# sch.net
KiCad netlist of a schematic drawn in EasyEDA
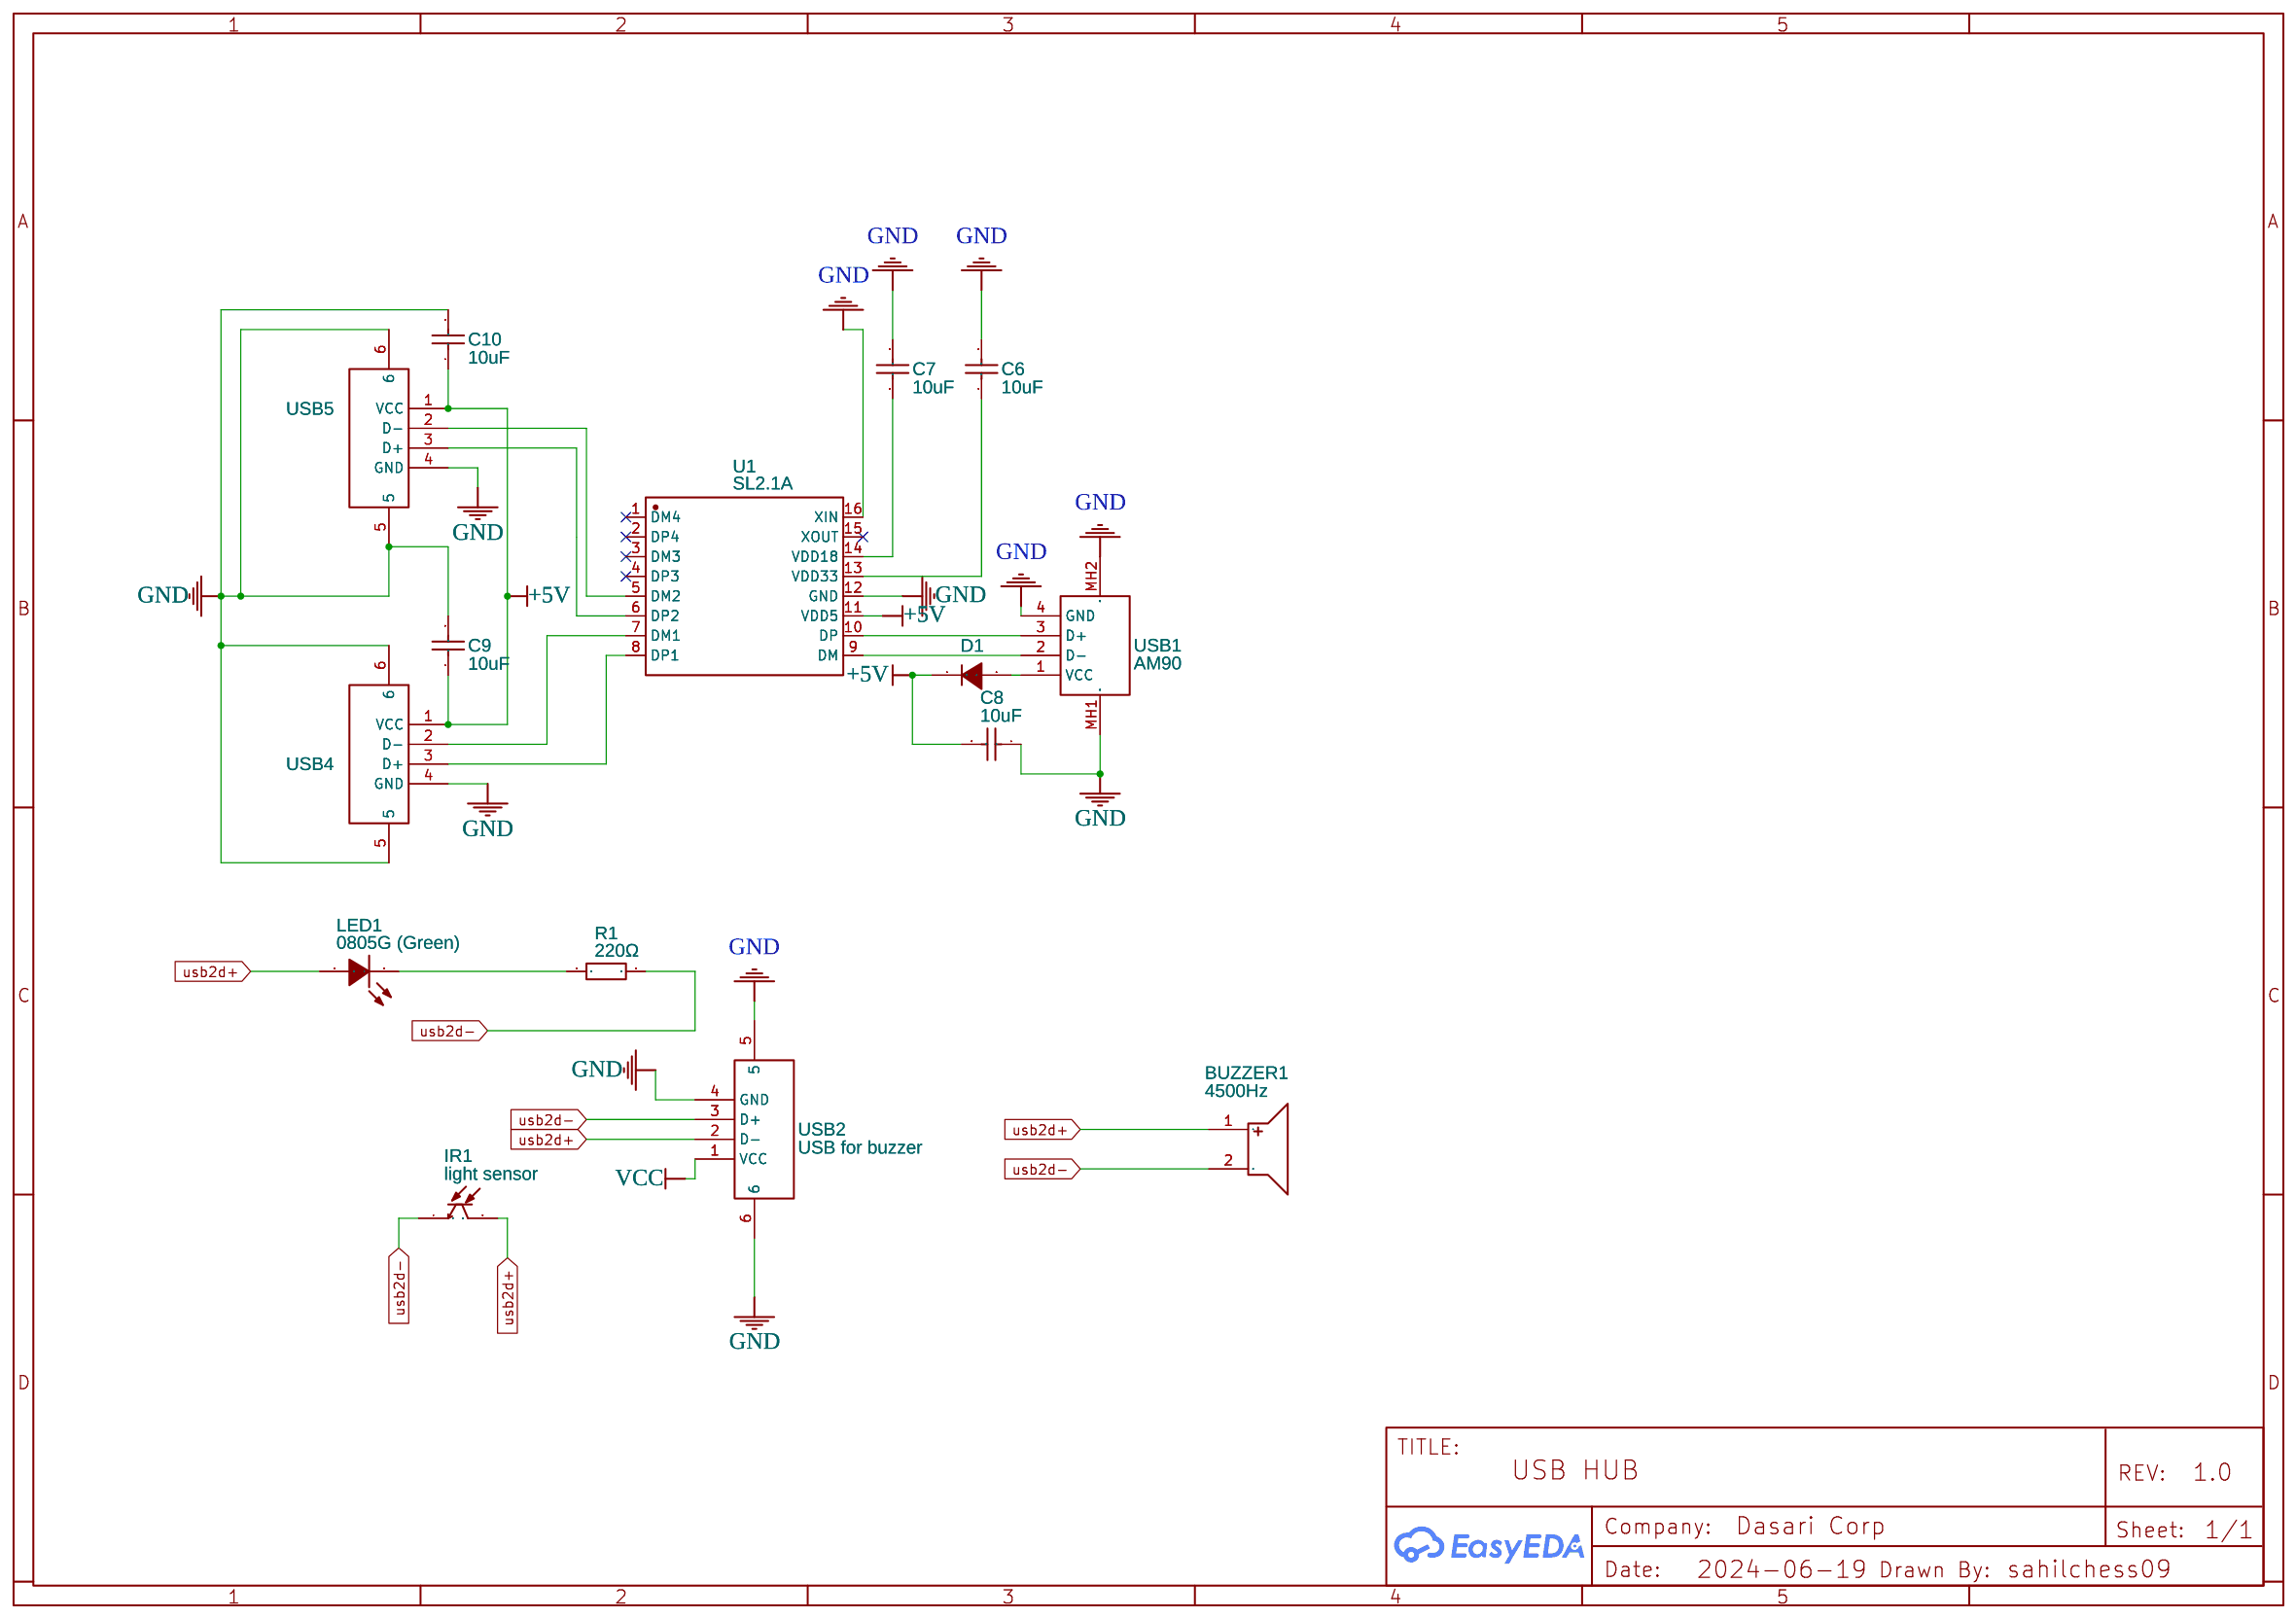
[diagram p0: schematic sheet]

(export (version "E")
  (design (tool "Eeschema 10.0.6"))
  (components
    (comp (ref "BUZZER1")
      (value "4500Hz")
      (fields (field (name "Manufacturer Part") "HND-1407B") (field (name "Manufacturer") "华能"))
      (libsource (lib "") (part "HND-1407B"))
    )
    (comp (ref "C6")
      (value "10uF")
      (fields
        (field (name "Manufacturer Part") "CL05A106MQ5NUNC")
        (field (name "Manufacturer") "SAMSUNG(三星)")
      )
      (libsource (lib "") (part "CL05A106MQ5NUNC"))
    )
    (comp (ref "C7")
      (value "10uF")
      (fields
        (field (name "Manufacturer Part") "CL05A106MQ5NUNC")
        (field (name "Manufacturer") "SAMSUNG(三星)")
      )
      (libsource (lib "") (part "CL05A106MQ5NUNC"))
    )
    (comp (ref "C8")
      (value "10uF")
      (fields
        (field (name "Manufacturer Part") "CL05A106MQ5NUNC")
        (field (name "Manufacturer") "SAMSUNG(三星)")
      )
      (libsource (lib "") (part "CL05A106MQ5NUNC_1"))
    )
    (comp (ref "C9")
      (value "10uF")
      (fields
        (field (name "Manufacturer Part") "CL05A106MQ5NUNC")
        (field (name "Manufacturer") "SAMSUNG(三星)")
      )
      (libsource (lib "") (part "CL05A106MQ5NUNC"))
    )
    (comp (ref "C10")
      (value "10uF")
      (fields
        (field (name "Manufacturer Part") "CL05A106MQ5NUNC")
        (field (name "Manufacturer") "SAMSUNG(三星)")
      )
      (libsource (lib "") (part "CL05A106MQ5NUNC"))
    )
    (comp (ref "D1")
      (value "‌")
      (fields (field (name "Manufacturer Part") "NSR0320MW2T1G") (field (name "Manufacturer") "onsemi(安森美)"))
      (libsource (lib "") (part "NSR0320MW2T1G"))
    )
    (comp (ref "IR1")
      (value "light sensor")
      (fields
        (field (name "Manufacturer Part") "PT928-6C(6-1)")
        (field (name "Manufacturer") "EVERLIGHT(亿光)")
      )
      (libsource (lib "") (part "PT928-6C(6-1)"))
    )
    (comp (ref "LED1")
      (value "0805G (Green)")
      (fields (field (name "Manufacturer Part") "KT-0805G") (field (name "Manufacturer") "KENTO"))
      (libsource (lib "") (part "0805G (Green)"))
    )
    (comp (ref "R1")
      (value "220Ω")
      (fields
        (field (name "Manufacturer Part") "0805W8F2200T5E")
        (field (name "Manufacturer") "UNI-ROYAL(厚声)")
      )
      (libsource (lib "") (part "0805W8F2200T5E"))
    )
    (comp (ref "U1")
      (value "SL2.1A")
      (fields (field (name "Manufacturer") "CoreChips(和芯润德)"))
      (libsource (lib "") (part "SL2.1A"))
    )
    (comp (ref "USB1")
      (value "AM90")
      (fields (field (name "Manufacturer") "SHOU HAN(首韩)"))
      (libsource (lib "") (part "AM90"))
    )
    (comp (ref "USB2")
      (value "USB for buzzer")
      (fields (field (name "Manufacturer Part") "903-131A1011D10100") (field (name "Manufacturer") "精拓金"))
      (libsource (lib "") (part "USB-AF-90-14.4X13.6-H7.0-DIP"))
    )
    (comp (ref "USB4")
      (value "USB-AF-90-14.4X13.6-H7.0-DIP")
      (fields (field (name "Manufacturer Part") "903-131A1011D10100") (field (name "Manufacturer") "精拓金"))
      (libsource (lib "") (part "USB-AF-90-14.4X13.6-H7.0-DIP_1"))
    )
    (comp (ref "USB5")
      (value "USB-AF-90-14.4X13.6-H7.0-DIP")
      (fields (field (name "Manufacturer Part") "903-131A1011D10100") (field (name "Manufacturer") "精拓金"))
      (libsource (lib "") (part "USB-AF-90-14.4X13.6-H7.0-DIP_1"))
    )
  )
  (nets
    (net (code "1") (name "+5V") (class "Default")
      (node (ref "C10") (pin "1") (pinfunction "1_1") (pintype "input"))
      (node (ref "C8") (pin "2") (pinfunction "2_2") (pintype "input"))
      (node (ref "C9") (pin "1") (pinfunction "1_1") (pintype "input"))
      (node (ref "D1") (pin "1") (pinfunction "C_1") (pintype "unspecified"))
      (node (ref "U1") (pin "11") (pinfunction "VDD5_11") (pintype "unspecified"))
      (node (ref "USB4") (pin "1") (pinfunction "VCC_1") (pintype "unspecified"))
      (node (ref "USB5") (pin "1") (pinfunction "VCC_1") (pintype "unspecified"))
    )
    (net (code "2") (name "GND") (class "Default")
      (node (ref "C10") (pin "2") (pinfunction "2_2") (pintype "input"))
      (node (ref "C6") (pin "2") (pinfunction "2_2") (pintype "input"))
      (node (ref "C7") (pin "2") (pinfunction "2_2") (pintype "input"))
      (node (ref "C8") (pin "1") (pinfunction "1_1") (pintype "input"))
      (node (ref "C9") (pin "2") (pinfunction "2_2") (pintype "input"))
      (node (ref "U1") (pin "12") (pinfunction "GND_12") (pintype "unspecified"))
      (node (ref "U1") (pin "16") (pinfunction "XIN_16") (pintype "unspecified"))
      (node (ref "USB1") (pin "4") (pinfunction "GND_4") (pintype "input"))
      (node (ref "USB1") (pin "MH1") (pinfunction "MH1_MH1") (pintype "unspecified"))
      (node (ref "USB1") (pin "MH2") (pinfunction "MH2_MH2") (pintype "unspecified"))
      (node (ref "USB2") (pin "4") (pinfunction "GND_4") (pintype "unspecified"))
      (node (ref "USB2") (pin "5") (pinfunction "5_5") (pintype "unspecified"))
      (node (ref "USB2") (pin "6") (pinfunction "6_6") (pintype "unspecified"))
      (node (ref "USB4") (pin "4") (pinfunction "GND_4") (pintype "unspecified"))
      (node (ref "USB4") (pin "5") (pinfunction "5_5") (pintype "unspecified"))
      (node (ref "USB4") (pin "6") (pinfunction "6_6") (pintype "unspecified"))
      (node (ref "USB5") (pin "4") (pinfunction "GND_4") (pintype "unspecified"))
      (node (ref "USB5") (pin "5") (pinfunction "5_5") (pintype "unspecified"))
      (node (ref "USB5") (pin "6") (pinfunction "6_6") (pintype "unspecified"))
    )
    (net (code "3") (name "Net-(D1-A)") (class "Default")
      (node (ref "D1") (pin "2") (pinfunction "A_2") (pintype "unspecified"))
      (node (ref "USB1") (pin "1") (pinfunction "VCC_1") (pintype "input"))
    )
    (net (code "4") (name "Net-(LED1-K)") (class "Default")
      (node (ref "LED1") (pin "2") (pinfunction "K_2") (pintype "unspecified"))
      (node (ref "R1") (pin "1") (pinfunction "1_1") (pintype "input"))
    )
    (net (code "5") (name "Net-(U1-DM)") (class "Default")
      (node (ref "U1") (pin "9") (pinfunction "DM_9") (pintype "unspecified"))
      (node (ref "USB1") (pin "2") (pinfunction "D-_2") (pintype "input"))
    )
    (net (code "6") (name "Net-(U1-DM1)") (class "Default")
      (node (ref "U1") (pin "7") (pinfunction "DM1_7") (pintype "unspecified"))
      (node (ref "USB4") (pin "2") (pinfunction "D-_2") (pintype "unspecified"))
    )
    (net (code "7") (name "Net-(U1-DM2)") (class "Default")
      (node (ref "U1") (pin "5") (pinfunction "DM2_5") (pintype "unspecified"))
      (node (ref "USB5") (pin "2") (pinfunction "D-_2") (pintype "unspecified"))
    )
    (net (code "8") (name "Net-(U1-DP)") (class "Default")
      (node (ref "U1") (pin "10") (pinfunction "DP_10") (pintype "unspecified"))
      (node (ref "USB1") (pin "3") (pinfunction "D+_3") (pintype "input"))
    )
    (net (code "9") (name "Net-(U1-DP1)") (class "Default")
      (node (ref "U1") (pin "8") (pinfunction "DP1_8") (pintype "unspecified"))
      (node (ref "USB4") (pin "3") (pinfunction "D+_3") (pintype "unspecified"))
    )
    (net (code "10") (name "Net-(U1-DP2)") (class "Default")
      (node (ref "U1") (pin "6") (pinfunction "DP2_6") (pintype "unspecified"))
      (node (ref "USB5") (pin "3") (pinfunction "D+_3") (pintype "unspecified"))
    )
    (net (code "11") (name "Net-(U1-VDD18)") (class "Default")
      (node (ref "C7") (pin "1") (pinfunction "1_1") (pintype "input"))
      (node (ref "U1") (pin "14") (pinfunction "VDD18_14") (pintype "unspecified"))
    )
    (net (code "12") (name "Net-(U1-VDD33)") (class "Default")
      (node (ref "C6") (pin "1") (pinfunction "1_1") (pintype "input"))
      (node (ref "U1") (pin "13") (pinfunction "VDD33_13") (pintype "unspecified"))
    )
    (net (code "13") (name "VCC") (class "Default")
      (node (ref "USB2") (pin "1") (pinfunction "VCC_1") (pintype "unspecified"))
    )
    (net (code "14") (name "unconnected-(U1-DM3-Pad3)") (class "Default")
      (node (ref "U1") (pin "3") (pinfunction "DM3_3") (pintype "unspecified+no_connect"))
    )
    (net (code "15") (name "unconnected-(U1-DM4-Pad1)") (class "Default")
      (node (ref "U1") (pin "1") (pinfunction "DM4_1") (pintype "unspecified+no_connect"))
    )
    (net (code "16") (name "unconnected-(U1-DP3-Pad4)") (class "Default")
      (node (ref "U1") (pin "4") (pinfunction "DP3_4") (pintype "unspecified+no_connect"))
    )
    (net (code "17") (name "unconnected-(U1-DP4-Pad2)") (class "Default")
      (node (ref "U1") (pin "2") (pinfunction "DP4_2") (pintype "unspecified+no_connect"))
    )
    (net (code "18") (name "unconnected-(U1-XOUT-Pad15)") (class "Default")
      (node (ref "U1") (pin "15") (pinfunction "XOUT_15") (pintype "unspecified+no_connect"))
    )
    (net (code "19") (name "usb2d+") (class "Default")
      (node (ref "BUZZER1") (pin "1") (pinfunction "1_1") (pintype "unspecified"))
      (node (ref "IR1") (pin "2") (pinfunction "C_2") (pintype "input"))
      (node (ref "LED1") (pin "1") (pinfunction "A_1") (pintype "unspecified"))
      (node (ref "USB2") (pin "2") (pinfunction "D-_2") (pintype "unspecified"))
    )
    (net (code "20") (name "usb2d-") (class "Default")
      (node (ref "BUZZER1") (pin "2") (pinfunction "2_2") (pintype "unspecified"))
      (node (ref "IR1") (pin "1") (pinfunction "E_1") (pintype "input"))
      (node (ref "R1") (pin "2") (pinfunction "2_2") (pintype "input"))
      (node (ref "USB2") (pin "3") (pinfunction "D+_3") (pintype "unspecified"))
    )
  )
)
